# Tracking_V0_1.net
KiCad netlist of a schematic drawn in EAGLE
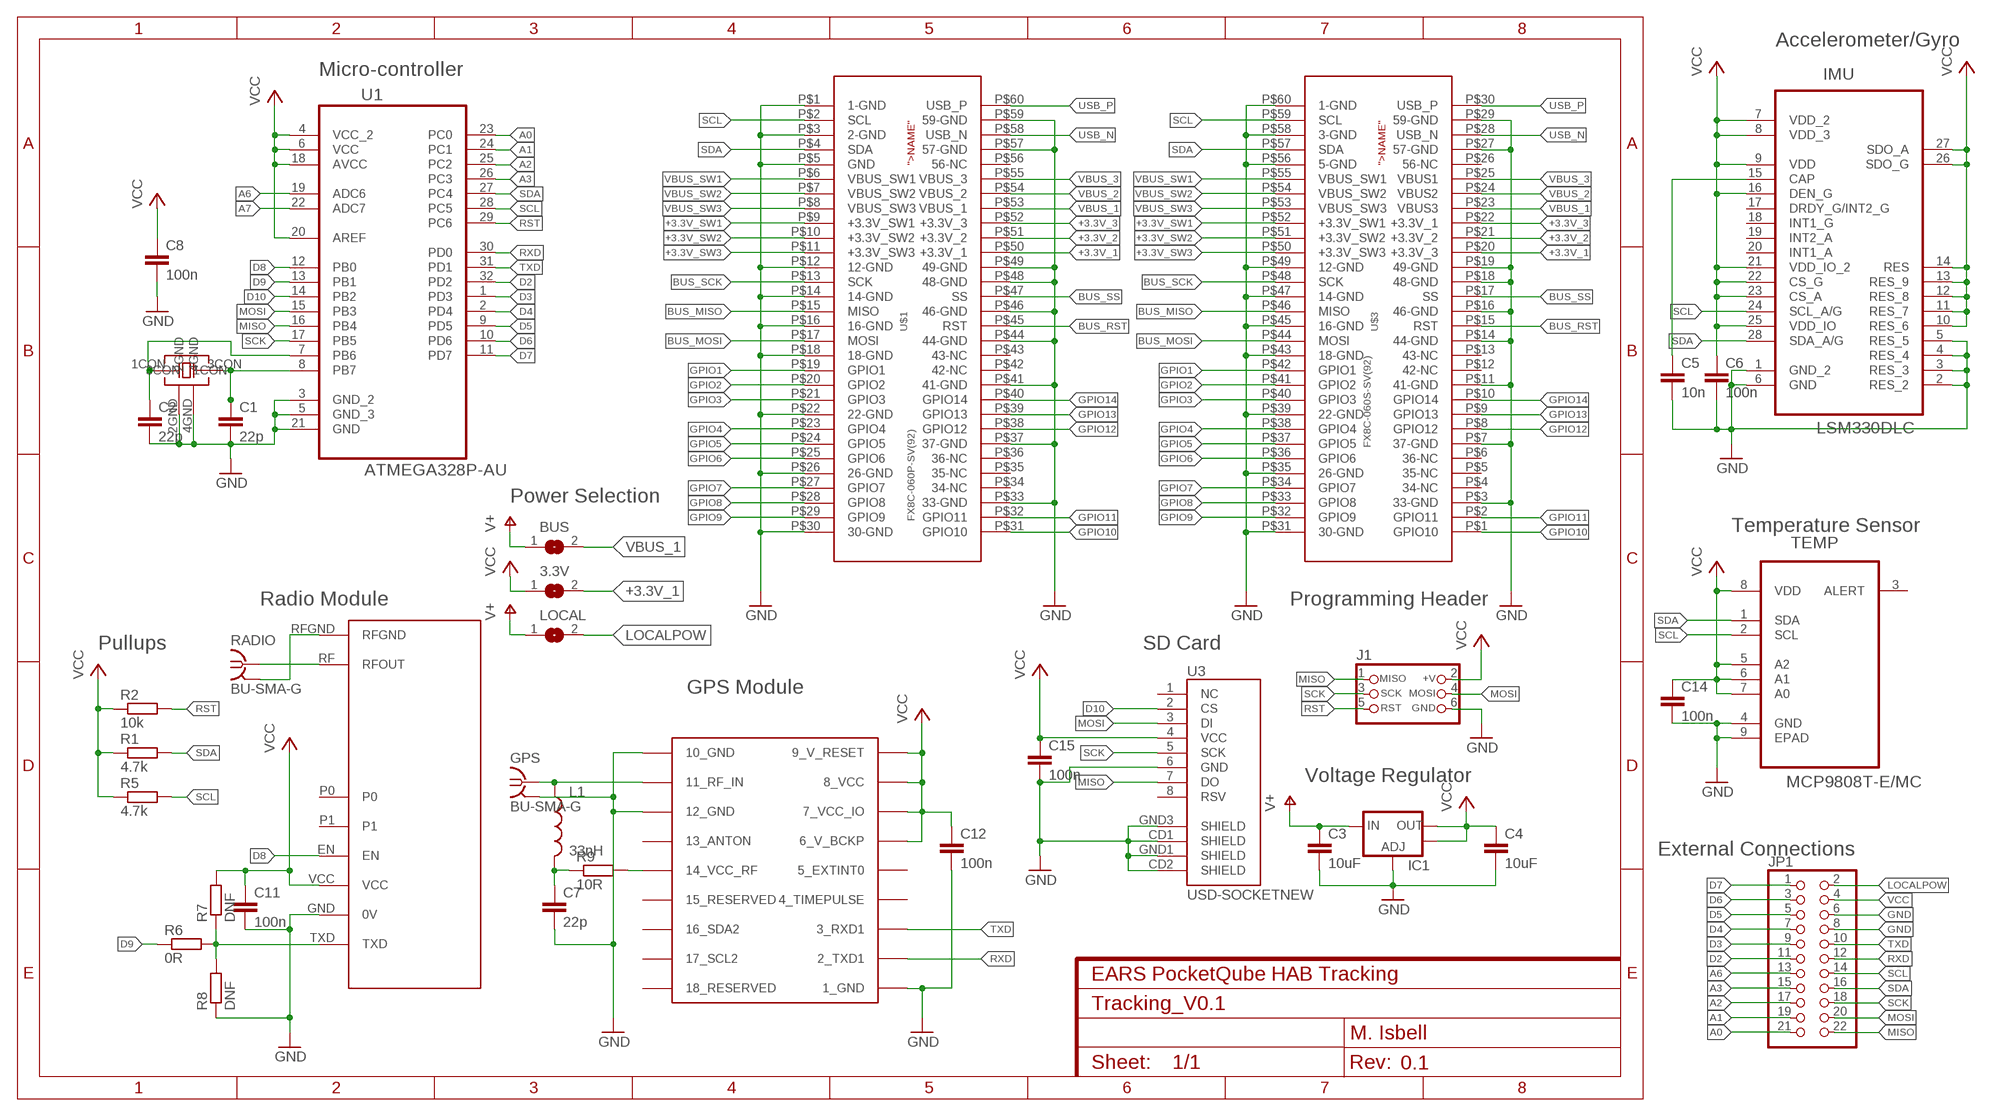
[diagram p0: schematic, sheet 1]

(export (version "E")
  (design (tool "Eeschema 10.0.6"))
  (components
    (comp (ref "3.3V")
      (value "SJ")
      (footprint "eagle-import:SJ")
      (libsource (lib "eagle-import") (part "SJ"))
    )
    (comp (ref "BUS") (value "SJ") (footprint "eagle-import:SJ") (libsource (lib "eagle-import") (part "SJ")))
    (comp (ref "C1")
      (value "22p")
      (footprint "eagle-import:C0603")
      (libsource (lib "eagle-import") (part "C-EUC0603"))
    )
    (comp (ref "C2")
      (value "22p")
      (footprint "eagle-import:C0603")
      (libsource (lib "eagle-import") (part "C-EUC0603"))
    )
    (comp (ref "C3")
      (value "10uF")
      (footprint "eagle-import:C0603")
      (libsource (lib "eagle-import") (part "C-EUC0603"))
    )
    (comp (ref "C4")
      (value "10uF")
      (footprint "eagle-import:C0603")
      (libsource (lib "eagle-import") (part "C-EUC0603"))
    )
    (comp (ref "C5")
      (value "10n")
      (footprint "eagle-import:C0603")
      (libsource (lib "eagle-import") (part "C-EUC0603"))
    )
    (comp (ref "C6")
      (value "100n")
      (footprint "eagle-import:C0603")
      (libsource (lib "eagle-import") (part "C-EUC0603"))
    )
    (comp (ref "C7")
      (value "22p")
      (footprint "eagle-import:C0603")
      (libsource (lib "eagle-import") (part "C-EUC0603"))
    )
    (comp (ref "C8")
      (value "100n")
      (footprint "eagle-import:C0603")
      (libsource (lib "eagle-import") (part "C-EUC0603"))
    )
    (comp (ref "C11")
      (value "100n")
      (footprint "eagle-import:C0603")
      (libsource (lib "eagle-import") (part "C-EUC0603"))
    )
    (comp (ref "C12")
      (value "100n")
      (footprint "eagle-import:C0603")
      (libsource (lib "eagle-import") (part "C-EUC0603"))
    )
    (comp (ref "C14")
      (value "100n")
      (footprint "eagle-import:C0603")
      (libsource (lib "eagle-import") (part "C-EUC0603"))
    )
    (comp (ref "C15")
      (value "100n")
      (footprint "eagle-import:C0603")
      (libsource (lib "eagle-import") (part "C-EUC0603"))
    )
    (comp (ref "GPS")
      (value "BU-SMA-G")
      (footprint "eagle-import:BU-SMA-G")
      (libsource (lib "eagle-import") (part "BU-SMA-G"))
    )
    (comp (ref "IC1")
      (value "V_REG_LM1117SOT223")
      (footprint "eagle-import:SOT223")
      (libsource (lib "eagle-import") (part "V_REG_LM1117SOT223"))
    )
    (comp (ref "IMU")
      (value "LSM330DLC")
      (footprint "eagle-import:LGA28R50P6X8_400X500X110")
      (libsource (lib "eagle-import") (part "LSM330DLC"))
    )
    (comp (ref "J1")
      (value "CON_HEADER_PRG_AVR_ICSP-PTH")
      (footprint "eagle-import:HEADER_PRG_2X03")
      (libsource (lib "eagle-import") (part "CON_HEADER_PRG_AVR_ICSP-PTH"))
    )
    (comp (ref "JP1")
      (value "PINHD-2X11")
      (footprint "eagle-import:2X11")
      (libsource (lib "eagle-import") (part "PINHD-2X11"))
    )
    (comp (ref "L1")
      (value "33nH")
      (footprint "eagle-import:0603")
      (libsource (lib "eagle-import") (part "INDUCTOR0603"))
    )
    (comp (ref "LOCAL")
      (value "SJ")
      (footprint "eagle-import:SJ")
      (libsource (lib "eagle-import") (part "SJ"))
    )
    (comp (ref "R1")
      (value "4.7k")
      (footprint "eagle-import:R0603")
      (libsource (lib "eagle-import") (part "R-EU_R0603"))
    )
    (comp (ref "R2")
      (value "10k")
      (footprint "eagle-import:R0603")
      (libsource (lib "eagle-import") (part "R-EU_R0603"))
    )
    (comp (ref "R5")
      (value "4.7k")
      (footprint "eagle-import:R0603")
      (libsource (lib "eagle-import") (part "R-EU_R0603"))
    )
    (comp (ref "R6")
      (value "0R")
      (footprint "eagle-import:R0603")
      (libsource (lib "eagle-import") (part "R-EU_R0603"))
    )
    (comp (ref "R7")
      (value "DNF")
      (footprint "eagle-import:R0603")
      (libsource (lib "eagle-import") (part "R-EU_R0603"))
    )
    (comp (ref "R8")
      (value "DNF")
      (footprint "eagle-import:R0603")
      (libsource (lib "eagle-import") (part "R-EU_R0603"))
    )
    (comp (ref "R9")
      (value "10R")
      (footprint "eagle-import:R0603")
      (libsource (lib "eagle-import") (part "R-EU_R0603"))
    )
    (comp (ref "RADIO")
      (value "BU-SMA-G")
      (footprint "eagle-import:BU-SMA-G")
      (libsource (lib "eagle-import") (part "BU-SMA-G"))
    )
    (comp (ref "TEMP")
      (value "MCP9808T-E/MC")
      (footprint "eagle-import:DFN300X200X100-9N")
      (libsource (lib "eagle-import") (part "MCP9808T-E/MC"))
    )
    (comp (ref "U$1")
      (value "FX8C-060P-SV(92)")
      (footprint "eagle-import:FX8C-060P-SV(92)")
      (libsource (lib "eagle-import") (part "FX8C-060P-SV(92)"))
    )
    (comp (ref "U$2")
      (value "CRYSTAL")
      (footprint "eagle-import:CRYSTAL")
      (libsource (lib "eagle-import") (part "CRYSTAL"))
    )
    (comp (ref "U$3")
      (value "FX8C-060S-SV(92)")
      (footprint "eagle-import:FX8C-060S-SV(92)")
      (libsource (lib "eagle-import") (part "FX8C-060S-SV(92)"))
    )
    (comp (ref "U$4")
      (value "UBLOX_MAX")
      (footprint "eagle-import:UBLOX_MAX")
      (libsource (lib "eagle-import") (part "UBLOX_MAX"))
    )
    (comp (ref "U$6")
      (value "RADIOMETRIX-MTX2")
      (footprint "eagle-import:RADIOMETRIX-MTX2")
      (libsource (lib "eagle-import") (part "RADIOMETRIX-MTX2"))
    )
    (comp (ref "U1")
      (value "ATMEGA328P-AU")
      (footprint "eagle-import:QFP80P900X900X120-32N")
      (libsource (lib "eagle-import") (part "ATMEGA328P-AU"))
    )
    (comp (ref "U3")
      (value "USD-SOCKETNEW")
      (footprint "eagle-import:MICRO-SD-SOCKET-PP")
      (libsource (lib "eagle-import") (part "USD-SOCKETNEW"))
    )
  )
  (nets
    (net (code "1") (name "+3.3V_1") (class "Default")
      (node (ref "3.3V") (pin "2") (pinfunction "2_2") (pintype "passive"))
      (node (ref "U$1") (pin "P$50") (pinfunction "+3.3V_1_P$50") (pintype "power_in"))
      (node (ref "U$3") (pin "P$20") (pinfunction "+3.3V_3_P$20") (pintype "power_in"))
    )
    (net (code "2") (name "+3.3V_2") (class "Default")
      (node (ref "U$1") (pin "P$51") (pinfunction "+3.3V_2_P$51") (pintype "power_in"))
      (node (ref "U$3") (pin "P$21") (pinfunction "+3.3V_2_P$21") (pintype "power_in"))
    )
    (net (code "3") (name "+3.3V_3") (class "Default")
      (node (ref "U$1") (pin "P$52") (pinfunction "+3.3V_3_P$52") (pintype "power_in"))
      (node (ref "U$3") (pin "P$22") (pinfunction "+3.3V_1_P$22") (pintype "power_in"))
    )
    (net (code "4") (name "+3.3V_SW1") (class "Default")
      (node (ref "U$1") (pin "P$9") (pinfunction "+3.3V_SW1_P$9") (pintype "power_in"))
      (node (ref "U$3") (pin "P$52") (pinfunction "+3.3V_SW1_P$52") (pintype "power_in"))
    )
    (net (code "5") (name "+3.3V_SW2") (class "Default")
      (node (ref "U$1") (pin "P$10") (pinfunction "+3.3V_SW2_P$10") (pintype "power_in"))
      (node (ref "U$3") (pin "P$51") (pinfunction "+3.3V_SW2_P$51") (pintype "power_in"))
    )
    (net (code "6") (name "+3.3V_SW3") (class "Default")
      (node (ref "U$1") (pin "P$11") (pinfunction "+3.3V_SW3_P$11") (pintype "power_in"))
      (node (ref "U$3") (pin "P$50") (pinfunction "+3.3V_SW3_P$50") (pintype "power_in"))
    )
    (net (code "7") (name "A0") (class "Default")
      (node (ref "JP1") (pin "21") (pinfunction "21_21") (pintype "passive"))
      (node (ref "U1") (pin "23") (pinfunction "PC0_23") (pintype "bidirectional"))
    )
    (net (code "8") (name "A1") (class "Default")
      (node (ref "JP1") (pin "19") (pinfunction "19_19") (pintype "passive"))
      (node (ref "U1") (pin "24") (pinfunction "PC1_24") (pintype "bidirectional"))
    )
    (net (code "9") (name "A2") (class "Default")
      (node (ref "JP1") (pin "17") (pinfunction "17_17") (pintype "passive"))
      (node (ref "U1") (pin "25") (pinfunction "PC2_25") (pintype "bidirectional"))
    )
    (net (code "10") (name "A3") (class "Default")
      (node (ref "JP1") (pin "15") (pinfunction "15_15") (pintype "passive"))
      (node (ref "U1") (pin "26") (pinfunction "PC3_26") (pintype "bidirectional"))
    )
    (net (code "11") (name "A6") (class "Default")
      (node (ref "JP1") (pin "13") (pinfunction "13_13") (pintype "passive"))
      (node (ref "U1") (pin "19") (pinfunction "ADC6_19") (pintype "input"))
    )
    (net (code "12") (name "A7") (class "Default")
      (node (ref "U1") (pin "22") (pinfunction "ADC7_22") (pintype "input"))
    )
    (net (code "13") (name "BUS_MISO") (class "Default")
      (node (ref "U$1") (pin "P$15") (pinfunction "MISO_P$15") (pintype "bidirectional"))
      (node (ref "U$3") (pin "P$46") (pinfunction "MISO_P$46") (pintype "bidirectional"))
    )
    (net (code "14") (name "BUS_MOSI") (class "Default")
      (node (ref "U$1") (pin "P$17") (pinfunction "MOSI_P$17") (pintype "bidirectional"))
      (node (ref "U$3") (pin "P$44") (pinfunction "MOSI_P$44") (pintype "bidirectional"))
    )
    (net (code "15") (name "BUS_RST") (class "Default")
      (node (ref "U$1") (pin "P$45") (pinfunction "RST_P$45") (pintype "bidirectional"))
      (node (ref "U$3") (pin "P$15") (pinfunction "RST_P$15") (pintype "bidirectional"))
    )
    (net (code "16") (name "BUS_SCK") (class "Default")
      (node (ref "U$1") (pin "P$13") (pinfunction "SCK_P$13") (pintype "bidirectional"))
      (node (ref "U$3") (pin "P$48") (pinfunction "SCK_P$48") (pintype "bidirectional"))
    )
    (net (code "17") (name "BUS_SS") (class "Default")
      (node (ref "U$1") (pin "P$47") (pinfunction "SS_P$47") (pintype "bidirectional"))
      (node (ref "U$3") (pin "P$17") (pinfunction "SS_P$17") (pintype "bidirectional"))
    )
    (net (code "18") (name "D2") (class "Default")
      (node (ref "JP1") (pin "11") (pinfunction "11_11") (pintype "passive"))
      (node (ref "U1") (pin "32") (pinfunction "PD2_32") (pintype "bidirectional"))
    )
    (net (code "19") (name "D3") (class "Default")
      (node (ref "JP1") (pin "9") (pinfunction "9_9") (pintype "passive"))
      (node (ref "U1") (pin "1") (pinfunction "PD3_1") (pintype "bidirectional"))
    )
    (net (code "20") (name "D4") (class "Default")
      (node (ref "JP1") (pin "7") (pinfunction "7_7") (pintype "passive"))
      (node (ref "U1") (pin "2") (pinfunction "PD4_2") (pintype "bidirectional"))
    )
    (net (code "21") (name "D5") (class "Default")
      (node (ref "JP1") (pin "5") (pinfunction "5_5") (pintype "passive"))
      (node (ref "U1") (pin "9") (pinfunction "PD5_9") (pintype "bidirectional"))
    )
    (net (code "22") (name "D6") (class "Default")
      (node (ref "JP1") (pin "3") (pinfunction "3_3") (pintype "passive"))
      (node (ref "U1") (pin "10") (pinfunction "PD6_10") (pintype "bidirectional"))
    )
    (net (code "23") (name "D7") (class "Default")
      (node (ref "JP1") (pin "1") (pinfunction "1_1") (pintype "passive"))
      (node (ref "U1") (pin "11") (pinfunction "PD7_11") (pintype "bidirectional"))
    )
    (net (code "24") (name "D8") (class "Default")
      (node (ref "U$6") (pin "EN") (pinfunction "EN_EN") (pintype "bidirectional"))
      (node (ref "U1") (pin "12") (pinfunction "PB0_12") (pintype "bidirectional"))
    )
    (net (code "25") (name "D9") (class "Default")
      (node (ref "R6") (pin "1") (pinfunction "1_1") (pintype "passive"))
      (node (ref "U1") (pin "13") (pinfunction "PB1_13") (pintype "bidirectional"))
    )
    (net (code "26") (name "D10") (class "Default")
      (node (ref "U1") (pin "14") (pinfunction "PB2_14") (pintype "bidirectional"))
      (node (ref "U3") (pin "2") (pinfunction "CS_2") (pintype "bidirectional"))
    )
    (net (code "27") (name "GND") (class "Default")
      (node (ref "C1") (pin "2") (pinfunction "2_2") (pintype "passive"))
      (node (ref "C11") (pin "2") (pinfunction "2_2") (pintype "passive"))
      (node (ref "C12") (pin "2") (pinfunction "2_2") (pintype "passive"))
      (node (ref "C14") (pin "2") (pinfunction "2_2") (pintype "passive"))
      (node (ref "C15") (pin "2") (pinfunction "2_2") (pintype "passive"))
      (node (ref "C2") (pin "2") (pinfunction "2_2") (pintype "passive"))
      (node (ref "C3") (pin "2") (pinfunction "2_2") (pintype "passive"))
      (node (ref "C4") (pin "2") (pinfunction "2_2") (pintype "passive"))
      (node (ref "C5") (pin "2") (pinfunction "2_2") (pintype "passive"))
      (node (ref "C6") (pin "2") (pinfunction "2_2") (pintype "passive"))
      (node (ref "C7") (pin "2") (pinfunction "2_2") (pintype "passive"))
      (node (ref "C8") (pin "2") (pinfunction "2_2") (pintype "passive"))
      (node (ref "GPS") (pin "2") (pinfunction "2_2") (pintype "passive"))
      (node (ref "GPS") (pin "3") (pinfunction "2_3") (pintype "passive"))
      (node (ref "GPS") (pin "4") (pinfunction "2_4") (pintype "passive"))
      (node (ref "GPS") (pin "5") (pinfunction "2_5") (pintype "passive"))
      (node (ref "IC1") (pin "1") (pinfunction "ADJ_1") (pintype "input"))
      (node (ref "IMU") (pin "1") (pinfunction "GND_2_1") (pintype "power_in"))
      (node (ref "IMU") (pin "2") (pinfunction "RES_2_2") (pintype "passive"))
      (node (ref "IMU") (pin "3") (pinfunction "RES_3_3") (pintype "passive"))
      (node (ref "IMU") (pin "4") (pinfunction "RES_4_4") (pintype "passive"))
      (node (ref "IMU") (pin "5") (pinfunction "RES_5_5") (pintype "passive"))
      (node (ref "IMU") (pin "6") (pinfunction "GND_6") (pintype "power_in"))
      (node (ref "J1") (pin "6") (pinfunction "GND_6") (pintype "passive"))
      (node (ref "JP1") (pin "6") (pinfunction "6_6") (pintype "passive"))
      (node (ref "JP1") (pin "8") (pinfunction "8_8") (pintype "passive"))
      (node (ref "R8") (pin "1") (pinfunction "1_1") (pintype "passive"))
      (node (ref "TEMP") (pin "4") (pinfunction "GND_4") (pintype "power_in"))
      (node (ref "TEMP") (pin "9") (pinfunction "EPAD_9") (pintype "passive"))
      (node (ref "U$1") (pin "P$1") (pinfunction "1-GND_P$1") (pintype "power_in"))
      (node (ref "U$1") (pin "P$12") (pinfunction "12-GND_P$12") (pintype "power_in"))
      (node (ref "U$1") (pin "P$14") (pinfunction "14-GND_P$14") (pintype "power_in"))
      (node (ref "U$1") (pin "P$16") (pinfunction "16-GND_P$16") (pintype "power_in"))
      (node (ref "U$1") (pin "P$18") (pinfunction "18-GND_P$18") (pintype "power_in"))
      (node (ref "U$1") (pin "P$22") (pinfunction "22-GND_P$22") (pintype "power_in"))
      (node (ref "U$1") (pin "P$26") (pinfunction "26-GND_P$26") (pintype "power_in"))
      (node (ref "U$1") (pin "P$3") (pinfunction "2-GND_P$3") (pintype "power_in"))
      (node (ref "U$1") (pin "P$30") (pinfunction "30-GND_P$30") (pintype "power_in"))
      (node (ref "U$1") (pin "P$33") (pinfunction "33-GND_P$33") (pintype "power_in"))
      (node (ref "U$1") (pin "P$37") (pinfunction "37-GND_P$37") (pintype "power_in"))
      (node (ref "U$1") (pin "P$41") (pinfunction "41-GND_P$41") (pintype "power_in"))
      (node (ref "U$1") (pin "P$44") (pinfunction "44-GND_P$44") (pintype "power_in"))
      (node (ref "U$1") (pin "P$46") (pinfunction "46-GND_P$46") (pintype "power_in"))
      (node (ref "U$1") (pin "P$48") (pinfunction "48-GND_P$48") (pintype "power_in"))
      (node (ref "U$1") (pin "P$49") (pinfunction "49-GND_P$49") (pintype "power_in"))
      (node (ref "U$1") (pin "P$5") (pinfunction "GND_P$5") (pintype "power_in"))
      (node (ref "U$1") (pin "P$57") (pinfunction "57-GND_P$57") (pintype "power_in"))
      (node (ref "U$1") (pin "P$59") (pinfunction "59-GND_P$59") (pintype "power_in"))
      (node (ref "U$2") (pin "2GND") (pinfunction "2GND_2GND") (pintype "bidirectional"))
      (node (ref "U$2") (pin "4GND") (pinfunction "4GND_4GND") (pintype "bidirectional"))
      (node (ref "U$3") (pin "P$11") (pinfunction "41-GND_P$11") (pintype "power_in"))
      (node (ref "U$3") (pin "P$14") (pinfunction "44-GND_P$14") (pintype "power_in"))
      (node (ref "U$3") (pin "P$16") (pinfunction "46-GND_P$16") (pintype "power_in"))
      (node (ref "U$3") (pin "P$18") (pinfunction "48-GND_P$18") (pintype "power_in"))
      (node (ref "U$3") (pin "P$19") (pinfunction "49-GND_P$19") (pintype "power_in"))
      (node (ref "U$3") (pin "P$27") (pinfunction "57-GND_P$27") (pintype "power_in"))
      (node (ref "U$3") (pin "P$29") (pinfunction "59-GND_P$29") (pintype "power_in"))
      (node (ref "U$3") (pin "P$3") (pinfunction "33-GND_P$3") (pintype "power_in"))
      (node (ref "U$3") (pin "P$31") (pinfunction "30-GND_P$31") (pintype "power_in"))
      (node (ref "U$3") (pin "P$35") (pinfunction "26-GND_P$35") (pintype "power_in"))
      (node (ref "U$3") (pin "P$39") (pinfunction "22-GND_P$39") (pintype "power_in"))
      (node (ref "U$3") (pin "P$43") (pinfunction "18-GND_P$43") (pintype "power_in"))
      (node (ref "U$3") (pin "P$45") (pinfunction "16-GND_P$45") (pintype "power_in"))
      (node (ref "U$3") (pin "P$47") (pinfunction "14-GND_P$47") (pintype "power_in"))
      (node (ref "U$3") (pin "P$49") (pinfunction "12-GND_P$49") (pintype "power_in"))
      (node (ref "U$3") (pin "P$56") (pinfunction "5-GND_P$56") (pintype "power_in"))
      (node (ref "U$3") (pin "P$58") (pinfunction "3-GND_P$58") (pintype "power_in"))
      (node (ref "U$3") (pin "P$60") (pinfunction "1-GND_P$60") (pintype "power_in"))
      (node (ref "U$3") (pin "P$7") (pinfunction "37-GND_P$7") (pintype "power_in"))
      (node (ref "U$4") (pin "10_GND") (pinfunction "10_GND_10_GND") (pintype "power_in"))
      (node (ref "U$4") (pin "12_GND") (pinfunction "12_GND_12_GND") (pintype "power_in"))
      (node (ref "U$4") (pin "1_GND") (pinfunction "1_GND_1_GND") (pintype "power_in"))
      (node (ref "U$6") (pin "GND") (pinfunction "0V_GND") (pintype "bidirectional"))
      (node (ref "U1") (pin "21") (pinfunction "GND_21") (pintype "passive"))
      (node (ref "U1") (pin "3") (pinfunction "GND_2_3") (pintype "passive"))
      (node (ref "U1") (pin "5") (pinfunction "GND_3_5") (pintype "passive"))
      (node (ref "U3") (pin "6") (pinfunction "GND_6") (pintype "bidirectional"))
      (node (ref "U3") (pin "CD1") (pinfunction "SHIELD_CD1") (pintype "bidirectional"))
      (node (ref "U3") (pin "CD2") (pinfunction "SHIELD_CD2") (pintype "bidirectional"))
      (node (ref "U3") (pin "GND1") (pinfunction "SHIELD_GND1") (pintype "bidirectional"))
      (node (ref "U3") (pin "GND3") (pinfunction "SHIELD_GND3") (pintype "bidirectional"))
    )
    (net (code "28") (name "GPIO1") (class "Default")
      (node (ref "U$1") (pin "P$19") (pinfunction "GPIO1_P$19") (pintype "bidirectional"))
      (node (ref "U$3") (pin "P$42") (pinfunction "GPIO1_P$42") (pintype "bidirectional"))
    )
    (net (code "29") (name "GPIO2") (class "Default")
      (node (ref "U$1") (pin "P$20") (pinfunction "GPIO2_P$20") (pintype "bidirectional"))
      (node (ref "U$3") (pin "P$41") (pinfunction "GPIO2_P$41") (pintype "bidirectional"))
    )
    (net (code "30") (name "GPIO3") (class "Default")
      (node (ref "U$1") (pin "P$21") (pinfunction "GPIO3_P$21") (pintype "bidirectional"))
      (node (ref "U$3") (pin "P$40") (pinfunction "GPIO3_P$40") (pintype "bidirectional"))
    )
    (net (code "31") (name "GPIO4") (class "Default")
      (node (ref "U$1") (pin "P$23") (pinfunction "GPIO4_P$23") (pintype "bidirectional"))
      (node (ref "U$3") (pin "P$38") (pinfunction "GPIO4_P$38") (pintype "bidirectional"))
    )
    (net (code "32") (name "GPIO5") (class "Default")
      (node (ref "U$1") (pin "P$24") (pinfunction "GPIO5_P$24") (pintype "bidirectional"))
      (node (ref "U$3") (pin "P$37") (pinfunction "GPIO5_P$37") (pintype "bidirectional"))
    )
    (net (code "33") (name "GPIO6") (class "Default")
      (node (ref "U$1") (pin "P$25") (pinfunction "GPIO6_P$25") (pintype "bidirectional"))
      (node (ref "U$3") (pin "P$36") (pinfunction "GPIO6_P$36") (pintype "bidirectional"))
    )
    (net (code "34") (name "GPIO7") (class "Default")
      (node (ref "U$1") (pin "P$27") (pinfunction "GPIO7_P$27") (pintype "bidirectional"))
      (node (ref "U$3") (pin "P$34") (pinfunction "GPIO7_P$34") (pintype "bidirectional"))
    )
    (net (code "35") (name "GPIO8") (class "Default")
      (node (ref "U$1") (pin "P$28") (pinfunction "GPIO8_P$28") (pintype "bidirectional"))
      (node (ref "U$3") (pin "P$33") (pinfunction "GPIO8_P$33") (pintype "bidirectional"))
    )
    (net (code "36") (name "GPIO9") (class "Default")
      (node (ref "U$1") (pin "P$29") (pinfunction "GPIO9_P$29") (pintype "bidirectional"))
      (node (ref "U$3") (pin "P$32") (pinfunction "GPIO9_P$32") (pintype "bidirectional"))
    )
    (net (code "37") (name "GPIO10") (class "Default")
      (node (ref "U$1") (pin "P$31") (pinfunction "GPIO10_P$31") (pintype "bidirectional"))
      (node (ref "U$3") (pin "P$1") (pinfunction "GPIO10_P$1") (pintype "bidirectional"))
    )
    (net (code "38") (name "GPIO11") (class "Default")
      (node (ref "U$1") (pin "P$32") (pinfunction "GPIO11_P$32") (pintype "bidirectional"))
      (node (ref "U$3") (pin "P$2") (pinfunction "GPIO11_P$2") (pintype "bidirectional"))
    )
    (net (code "39") (name "GPIO12") (class "Default")
      (node (ref "U$1") (pin "P$38") (pinfunction "GPIO12_P$38") (pintype "bidirectional"))
      (node (ref "U$3") (pin "P$8") (pinfunction "GPIO12_P$8") (pintype "bidirectional"))
    )
    (net (code "40") (name "GPIO13") (class "Default")
      (node (ref "U$1") (pin "P$39") (pinfunction "GPIO13_P$39") (pintype "bidirectional"))
      (node (ref "U$3") (pin "P$9") (pinfunction "GPIO13_P$9") (pintype "bidirectional"))
    )
    (net (code "41") (name "GPIO14") (class "Default")
      (node (ref "U$1") (pin "P$40") (pinfunction "GPIO14_P$40") (pintype "bidirectional"))
      (node (ref "U$3") (pin "P$10") (pinfunction "GPIO14_P$10") (pintype "bidirectional"))
    )
    (net (code "42") (name "LOCALPOW") (class "Default")
      (node (ref "JP1") (pin "2") (pinfunction "2_2") (pintype "passive"))
      (node (ref "LOCAL") (pin "2") (pinfunction "2_2") (pintype "passive"))
    )
    (net (code "43") (name "MISO") (class "Default")
      (node (ref "J1") (pin "1") (pinfunction "MISO_1") (pintype "passive"))
      (node (ref "JP1") (pin "22") (pinfunction "22_22") (pintype "passive"))
      (node (ref "U1") (pin "16") (pinfunction "PB4_16") (pintype "bidirectional"))
      (node (ref "U3") (pin "7") (pinfunction "DO_7") (pintype "bidirectional"))
    )
    (net (code "44") (name "MOSI") (class "Default")
      (node (ref "J1") (pin "4") (pinfunction "MOSI_4") (pintype "passive"))
      (node (ref "JP1") (pin "20") (pinfunction "20_20") (pintype "passive"))
      (node (ref "U1") (pin "15") (pinfunction "PB3_15") (pintype "bidirectional"))
      (node (ref "U3") (pin "3") (pinfunction "DI_3") (pintype "bidirectional"))
    )
    (net (code "45") (name "Net-(C7-Pad1)") (class "Default")
      (node (ref "C7") (pin "1") (pinfunction "1_1") (pintype "passive"))
      (node (ref "L1") (pin "2") (pinfunction "2_2") (pintype "passive"))
      (node (ref "R9") (pin "1") (pinfunction "1_1") (pintype "passive"))
    )
    (net (code "46") (name "Net-(GPS-Pad1)") (class "Default")
      (node (ref "GPS") (pin "1") (pinfunction "1_1") (pintype "passive"))
      (node (ref "L1") (pin "1") (pinfunction "1_1") (pintype "passive"))
      (node (ref "U$4") (pin "11_RF_IN") (pinfunction "11_RF_IN_11_RF_IN") (pintype "bidirectional"))
    )
    (net (code "47") (name "Net-(IMU-CAP)") (class "Default")
      (node (ref "C5") (pin "1") (pinfunction "1_1") (pintype "passive"))
      (node (ref "IMU") (pin "15") (pinfunction "CAP_15") (pintype "passive"))
    )
    (net (code "48") (name "Net-(R6-Pad2)") (class "Default")
      (node (ref "R6") (pin "2") (pinfunction "2_2") (pintype "passive"))
      (node (ref "R7") (pin "1") (pinfunction "1_1") (pintype "passive"))
      (node (ref "R8") (pin "2") (pinfunction "2_2") (pintype "passive"))
      (node (ref "U$6") (pin "TXD") (pinfunction "TXD_TXD") (pintype "bidirectional"))
    )
    (net (code "49") (name "Net-(R9-Pad2)") (class "Default")
      (node (ref "R9") (pin "2") (pinfunction "2_2") (pintype "passive"))
      (node (ref "U$4") (pin "14_VCC_RF") (pinfunction "14_VCC_RF_14_VCC_RF") (pintype "bidirectional"))
    )
    (net (code "50") (name "Net-(RADIO-2-Pad3)") (class "Default")
      (node (ref "RADIO") (pin "2") (pinfunction "2_2") (pintype "passive"))
      (node (ref "RADIO") (pin "3") (pinfunction "2_3") (pintype "passive"))
      (node (ref "RADIO") (pin "4") (pinfunction "2_4") (pintype "passive"))
      (node (ref "RADIO") (pin "5") (pinfunction "2_5") (pintype "passive"))
      (node (ref "U$6") (pin "RFGND") (pinfunction "RFGND_RFGND") (pintype "bidirectional"))
    )
    (net (code "51") (name "Net-(U$6-RFOUT)") (class "Default")
      (node (ref "RADIO") (pin "1") (pinfunction "1_1") (pintype "passive"))
      (node (ref "U$6") (pin "RF") (pinfunction "RFOUT_RF") (pintype "bidirectional"))
    )
    (net (code "52") (name "Net-(U1-PB6)") (class "Default")
      (node (ref "C2") (pin "1") (pinfunction "1_1") (pintype "passive"))
      (node (ref "U$2") (pin "1CON") (pinfunction "1CON_1CON") (pintype "bidirectional"))
      (node (ref "U1") (pin "7") (pinfunction "PB6_7") (pintype "bidirectional"))
    )
    (net (code "53") (name "Net-(U1-PB7)") (class "Default")
      (node (ref "C1") (pin "1") (pinfunction "1_1") (pintype "passive"))
      (node (ref "U$2") (pin "3CON") (pinfunction "3CON_3CON") (pintype "bidirectional"))
      (node (ref "U1") (pin "8") (pinfunction "PB7_8") (pintype "bidirectional"))
    )
    (net (code "54") (name "RST") (class "Default")
      (node (ref "J1") (pin "5") (pinfunction "RST_5") (pintype "passive"))
      (node (ref "R2") (pin "2") (pinfunction "2_2") (pintype "passive"))
      (node (ref "U1") (pin "29") (pinfunction "PC6_29") (pintype "bidirectional"))
    )
    (net (code "55") (name "RXD") (class "Default")
      (node (ref "JP1") (pin "12") (pinfunction "12_12") (pintype "passive"))
      (node (ref "U$4") (pin "2_TXD1") (pinfunction "2_TXD1_2_TXD1") (pintype "bidirectional"))
      (node (ref "U1") (pin "30") (pinfunction "PD0_30") (pintype "bidirectional"))
    )
    (net (code "56") (name "SCK") (class "Default")
      (node (ref "J1") (pin "3") (pinfunction "SCK_3") (pintype "passive"))
      (node (ref "JP1") (pin "18") (pinfunction "18_18") (pintype "passive"))
      (node (ref "U1") (pin "17") (pinfunction "PB5_17") (pintype "bidirectional"))
      (node (ref "U3") (pin "5") (pinfunction "SCK_5") (pintype "bidirectional"))
    )
    (net (code "57") (name "SCL") (class "Default")
      (node (ref "IMU") (pin "24") (pinfunction "SCL_A/G_24") (pintype "passive"))
      (node (ref "JP1") (pin "14") (pinfunction "14_14") (pintype "passive"))
      (node (ref "R5") (pin "2") (pinfunction "2_2") (pintype "passive"))
      (node (ref "TEMP") (pin "2") (pinfunction "SCL_2") (pintype "input"))
      (node (ref "U$1") (pin "P$2") (pinfunction "SCL_P$2") (pintype "bidirectional"))
      (node (ref "U$3") (pin "P$59") (pinfunction "SCL_P$59") (pintype "bidirectional"))
      (node (ref "U1") (pin "28") (pinfunction "PC5_28") (pintype "bidirectional"))
    )
    (net (code "58") (name "SDA") (class "Default")
      (node (ref "IMU") (pin "28") (pinfunction "SDA_A/G_28") (pintype "passive"))
      (node (ref "JP1") (pin "16") (pinfunction "16_16") (pintype "passive"))
      (node (ref "R1") (pin "2") (pinfunction "2_2") (pintype "passive"))
      (node (ref "TEMP") (pin "1") (pinfunction "SDA_1") (pintype "input"))
      (node (ref "U$1") (pin "P$4") (pinfunction "SDA_P$4") (pintype "bidirectional"))
      (node (ref "U$3") (pin "P$57") (pinfunction "SDA_P$57") (pintype "bidirectional"))
      (node (ref "U1") (pin "27") (pinfunction "PC4_27") (pintype "bidirectional"))
    )
    (net (code "59") (name "TXD") (class "Default")
      (node (ref "JP1") (pin "10") (pinfunction "10_10") (pintype "passive"))
      (node (ref "U$4") (pin "3_RXD1") (pinfunction "3_RXD1_3_RXD1") (pintype "bidirectional"))
      (node (ref "U1") (pin "31") (pinfunction "PD1_31") (pintype "bidirectional"))
    )
    (net (code "60") (name "USB_N") (class "Default")
      (node (ref "U$1") (pin "P$58") (pinfunction "USB_N_P$58") (pintype "bidirectional"))
      (node (ref "U$3") (pin "P$28") (pinfunction "USB_N_P$28") (pintype "bidirectional"))
    )
    (net (code "61") (name "USB_P") (class "Default")
      (node (ref "U$1") (pin "P$60") (pinfunction "USB_P_P$60") (pintype "bidirectional"))
      (node (ref "U$3") (pin "P$30") (pinfunction "USB_P_P$30") (pintype "bidirectional"))
    )
    (net (code "62") (name "V+") (class "Default")
      (node (ref "BUS") (pin "1") (pinfunction "1_1") (pintype "passive"))
      (node (ref "C3") (pin "1") (pinfunction "1_1") (pintype "passive"))
      (node (ref "IC1") (pin "3") (pinfunction "IN_3") (pintype "input"))
      (node (ref "LOCAL") (pin "1") (pinfunction "1_1") (pintype "passive"))
    )
    (net (code "63") (name "VBUS_1") (class "Default")
      (node (ref "BUS") (pin "2") (pinfunction "2_2") (pintype "passive"))
      (node (ref "U$1") (pin "P$53") (pinfunction "VBUS_1_P$53") (pintype "power_in"))
      (node (ref "U$3") (pin "P$23") (pinfunction "VBUS3_P$23") (pintype "bidirectional"))
    )
    (net (code "64") (name "VBUS_2") (class "Default")
      (node (ref "U$1") (pin "P$54") (pinfunction "VBUS_2_P$54") (pintype "power_in"))
      (node (ref "U$3") (pin "P$24") (pinfunction "VBUS2_P$24") (pintype "power_in"))
    )
    (net (code "65") (name "VBUS_3") (class "Default")
      (node (ref "U$1") (pin "P$55") (pinfunction "VBUS_3_P$55") (pintype "power_in"))
      (node (ref "U$3") (pin "P$25") (pinfunction "VBUS1_P$25") (pintype "open_collector"))
    )
    (net (code "66") (name "VBUS_SW1") (class "Default")
      (node (ref "U$1") (pin "P$6") (pinfunction "VBUS_SW1_P$6") (pintype "power_in"))
      (node (ref "U$3") (pin "P$55") (pinfunction "VBUS_SW1_P$55") (pintype "power_in"))
    )
    (net (code "67") (name "VBUS_SW2") (class "Default")
      (node (ref "U$1") (pin "P$7") (pinfunction "VBUS_SW2_P$7") (pintype "power_in"))
      (node (ref "U$3") (pin "P$54") (pinfunction "VBUS_SW2_P$54") (pintype "power_in"))
    )
    (net (code "68") (name "VBUS_SW3") (class "Default")
      (node (ref "U$1") (pin "P$8") (pinfunction "VBUS_SW3_P$8") (pintype "power_in"))
      (node (ref "U$3") (pin "P$53") (pinfunction "VBUS_SW3_P$53") (pintype "power_in"))
    )
    (net (code "69") (name "VCC") (class "Default")
      (node (ref "3.3V") (pin "1") (pinfunction "1_1") (pintype "passive"))
      (node (ref "C11") (pin "1") (pinfunction "1_1") (pintype "passive"))
      (node (ref "C12") (pin "1") (pinfunction "1_1") (pintype "passive"))
      (node (ref "C14") (pin "1") (pinfunction "1_1") (pintype "passive"))
      (node (ref "C15") (pin "1") (pinfunction "1_1") (pintype "passive"))
      (node (ref "C4") (pin "1") (pinfunction "1_1") (pintype "passive"))
      (node (ref "C6") (pin "1") (pinfunction "1_1") (pintype "passive"))
      (node (ref "C8") (pin "1") (pinfunction "1_1") (pintype "passive"))
      (node (ref "IC1") (pin "2") (pinfunction "OUT_2") (pintype "output"))
      (node (ref "IC1") (pin "4") (pinfunction "OUT_4") (pintype "output"))
      (node (ref "IMU") (pin "10") (pinfunction "RES_6_10") (pintype "passive"))
      (node (ref "IMU") (pin "11") (pinfunction "RES_7_11") (pintype "passive"))
      (node (ref "IMU") (pin "12") (pinfunction "RES_8_12") (pintype "passive"))
      (node (ref "IMU") (pin "13") (pinfunction "RES_9_13") (pintype "passive"))
      (node (ref "IMU") (pin "14") (pinfunction "RES_14") (pintype "passive"))
      (node (ref "IMU") (pin "16") (pinfunction "DEN_G_16") (pintype "passive"))
      (node (ref "IMU") (pin "21") (pinfunction "VDD_IO_2_21") (pintype "power_in"))
      (node (ref "IMU") (pin "22") (pinfunction "CS_G_22") (pintype "passive"))
      (node (ref "IMU") (pin "23") (pinfunction "CS_A_23") (pintype "passive"))
      (node (ref "IMU") (pin "25") (pinfunction "VDD_IO_25") (pintype "power_in"))
      (node (ref "IMU") (pin "26") (pinfunction "SDO_G_26") (pintype "passive"))
      (node (ref "IMU") (pin "27") (pinfunction "SDO_A_27") (pintype "passive"))
      (node (ref "IMU") (pin "7") (pinfunction "VDD_2_7") (pintype "power_in"))
      (node (ref "IMU") (pin "8") (pinfunction "VDD_3_8") (pintype "power_in"))
      (node (ref "IMU") (pin "9") (pinfunction "VDD_9") (pintype "power_in"))
      (node (ref "J1") (pin "2") (pinfunction "+V_2") (pintype "passive"))
      (node (ref "JP1") (pin "4") (pinfunction "4_4") (pintype "passive"))
      (node (ref "R1") (pin "1") (pinfunction "1_1") (pintype "passive"))
      (node (ref "R2") (pin "1") (pinfunction "1_1") (pintype "passive"))
      (node (ref "R5") (pin "1") (pinfunction "1_1") (pintype "passive"))
      (node (ref "R7") (pin "2") (pinfunction "2_2") (pintype "passive"))
      (node (ref "TEMP") (pin "5") (pinfunction "A2_5") (pintype "input"))
      (node (ref "TEMP") (pin "6") (pinfunction "A1_6") (pintype "input"))
      (node (ref "TEMP") (pin "7") (pinfunction "A0_7") (pintype "input"))
      (node (ref "TEMP") (pin "8") (pinfunction "VDD_8") (pintype "power_in"))
      (node (ref "U$4") (pin "6_V_BCKP") (pinfunction "6_V_BCKP_6_V_BCKP") (pintype "bidirectional"))
      (node (ref "U$4") (pin "7_VCC_IO") (pinfunction "7_VCC_IO_7_VCC_IO") (pintype "power_in"))
      (node (ref "U$4") (pin "8_VCC") (pinfunction "8_VCC_8_VCC") (pintype "power_in"))
      (node (ref "U$4") (pin "9_V_RESET") (pinfunction "9_V_RESET_9_V_RESET") (pintype "power_in"))
      (node (ref "U$6") (pin "VCC") (pinfunction "VCC_VCC") (pintype "bidirectional"))
      (node (ref "U1") (pin "18") (pinfunction "AVCC_18") (pintype "power_in"))
      (node (ref "U1") (pin "20") (pinfunction "AREF_20") (pintype "input"))
      (node (ref "U1") (pin "4") (pinfunction "VCC_2_4") (pintype "power_in"))
      (node (ref "U1") (pin "6") (pinfunction "VCC_6") (pintype "power_in"))
      (node (ref "U3") (pin "4") (pinfunction "VCC_4") (pintype "bidirectional"))
    )
    (net (code "70") (name "unconnected-(IMU-DRDY_G{slash}INT2_G-Pad17)") (class "Default")
      (node (ref "IMU") (pin "17") (pinfunction "DRDY_G/INT2_G_17") (pintype "passive"))
    )
    (net (code "71") (name "unconnected-(IMU-INT1_A-Pad20)") (class "Default")
      (node (ref "IMU") (pin "20") (pinfunction "INT1_A_20") (pintype "passive"))
    )
    (net (code "72") (name "unconnected-(IMU-INT1_G-Pad18)") (class "Default")
      (node (ref "IMU") (pin "18") (pinfunction "INT1_G_18") (pintype "passive"))
    )
    (net (code "73") (name "unconnected-(IMU-INT2_A-Pad19)") (class "Default")
      (node (ref "IMU") (pin "19") (pinfunction "INT2_A_19") (pintype "passive"))
    )
    (net (code "74") (name "unconnected-(TEMP-ALERT-Pad3)") (class "Default")
      (node (ref "TEMP") (pin "3") (pinfunction "ALERT_3") (pintype "output"))
    )
    (net (code "75") (name "unconnected-(U$1-34-NC-PadP$34)") (class "Default")
      (node (ref "U$1") (pin "P$34") (pinfunction "34-NC_P$34") (pintype "no_connect"))
    )
    (net (code "76") (name "unconnected-(U$1-35-NC-PadP$35)") (class "Default")
      (node (ref "U$1") (pin "P$35") (pinfunction "35-NC_P$35") (pintype "no_connect"))
    )
    (net (code "77") (name "unconnected-(U$1-36-NC-PadP$36)") (class "Default")
      (node (ref "U$1") (pin "P$36") (pinfunction "36-NC_P$36") (pintype "no_connect"))
    )
    (net (code "78") (name "unconnected-(U$1-42-NC-PadP$42)") (class "Default")
      (node (ref "U$1") (pin "P$42") (pinfunction "42-NC_P$42") (pintype "no_connect"))
    )
    (net (code "79") (name "unconnected-(U$1-43-NC-PadP$43)") (class "Default")
      (node (ref "U$1") (pin "P$43") (pinfunction "43-NC_P$43") (pintype "no_connect"))
    )
    (net (code "80") (name "unconnected-(U$1-56-NC-PadP$56)") (class "Default")
      (node (ref "U$1") (pin "P$56") (pinfunction "56-NC_P$56") (pintype "no_connect"))
    )
    (net (code "81") (name "unconnected-(U$3-34-NC-PadP$4)") (class "Default")
      (node (ref "U$3") (pin "P$4") (pinfunction "34-NC_P$4") (pintype "no_connect"))
    )
    (net (code "82") (name "unconnected-(U$3-35-NC-PadP$5)") (class "Default")
      (node (ref "U$3") (pin "P$5") (pinfunction "35-NC_P$5") (pintype "no_connect"))
    )
    (net (code "83") (name "unconnected-(U$3-36-NC-PadP$6)") (class "Default")
      (node (ref "U$3") (pin "P$6") (pinfunction "36-NC_P$6") (pintype "no_connect"))
    )
    (net (code "84") (name "unconnected-(U$3-42-NC-PadP$12)") (class "Default")
      (node (ref "U$3") (pin "P$12") (pinfunction "42-NC_P$12") (pintype "no_connect"))
    )
    (net (code "85") (name "unconnected-(U$3-43-NC-PadP$13)") (class "Default")
      (node (ref "U$3") (pin "P$13") (pinfunction "43-NC_P$13") (pintype "no_connect"))
    )
    (net (code "86") (name "unconnected-(U$3-56-NC-PadP$26)") (class "Default")
      (node (ref "U$3") (pin "P$26") (pinfunction "56-NC_P$26") (pintype "no_connect"))
    )
    (net (code "87") (name "unconnected-(U$4-Pad4_TIMEPULSE)") (class "Default")
      (node (ref "U$4") (pin "4_TIMEPULSE") (pinfunction "4_TIMEPULSE_4_TIMEPULSE") (pintype "bidirectional"))
    )
    (net (code "88") (name "unconnected-(U$4-Pad5_EXTINT0)") (class "Default")
      (node (ref "U$4") (pin "5_EXTINT0") (pinfunction "5_EXTINT0_5_EXTINT0") (pintype "bidirectional"))
    )
    (net (code "89") (name "unconnected-(U$4-Pad13_ANTON)") (class "Default")
      (node (ref "U$4") (pin "13_ANTON") (pinfunction "13_ANTON_13_ANTON") (pintype "bidirectional"))
    )
    (net (code "90") (name "unconnected-(U$4-Pad15_RESERVED)") (class "Default")
      (node (ref "U$4") (pin "15_RESERVED") (pinfunction "15_RESERVED_15_RESERVED") (pintype "bidirectional"))
    )
    (net (code "91") (name "unconnected-(U$4-Pad16_SDA2)") (class "Default")
      (node (ref "U$4") (pin "16_SDA2") (pinfunction "16_SDA2_16_SDA2") (pintype "bidirectional"))
    )
    (net (code "92") (name "unconnected-(U$4-Pad17_SCL2)") (class "Default")
      (node (ref "U$4") (pin "17_SCL2") (pinfunction "17_SCL2_17_SCL2") (pintype "bidirectional"))
    )
    (net (code "93") (name "unconnected-(U$4-Pad18_RESERVED)") (class "Default")
      (node (ref "U$4") (pin "18_RESERVED") (pinfunction "18_RESERVED_18_RESERVED") (pintype "bidirectional"))
    )
    (net (code "94") (name "unconnected-(U$6-PadP0)") (class "Default")
      (node (ref "U$6") (pin "P0") (pinfunction "P0_P0") (pintype "bidirectional"))
    )
    (net (code "95") (name "unconnected-(U$6-PadP1)") (class "Default")
      (node (ref "U$6") (pin "P1") (pinfunction "P1_P1") (pintype "bidirectional"))
    )
    (net (code "96") (name "unconnected-(U3-NC-Pad1)") (class "Default")
      (node (ref "U3") (pin "1") (pinfunction "NC_1") (pintype "bidirectional"))
    )
    (net (code "97") (name "unconnected-(U3-RSV-Pad8)") (class "Default")
      (node (ref "U3") (pin "8") (pinfunction "RSV_8") (pintype "bidirectional"))
    )
  )
)
